# prj1.net
KiCad netlist of a schematic drawn in Altium Designer
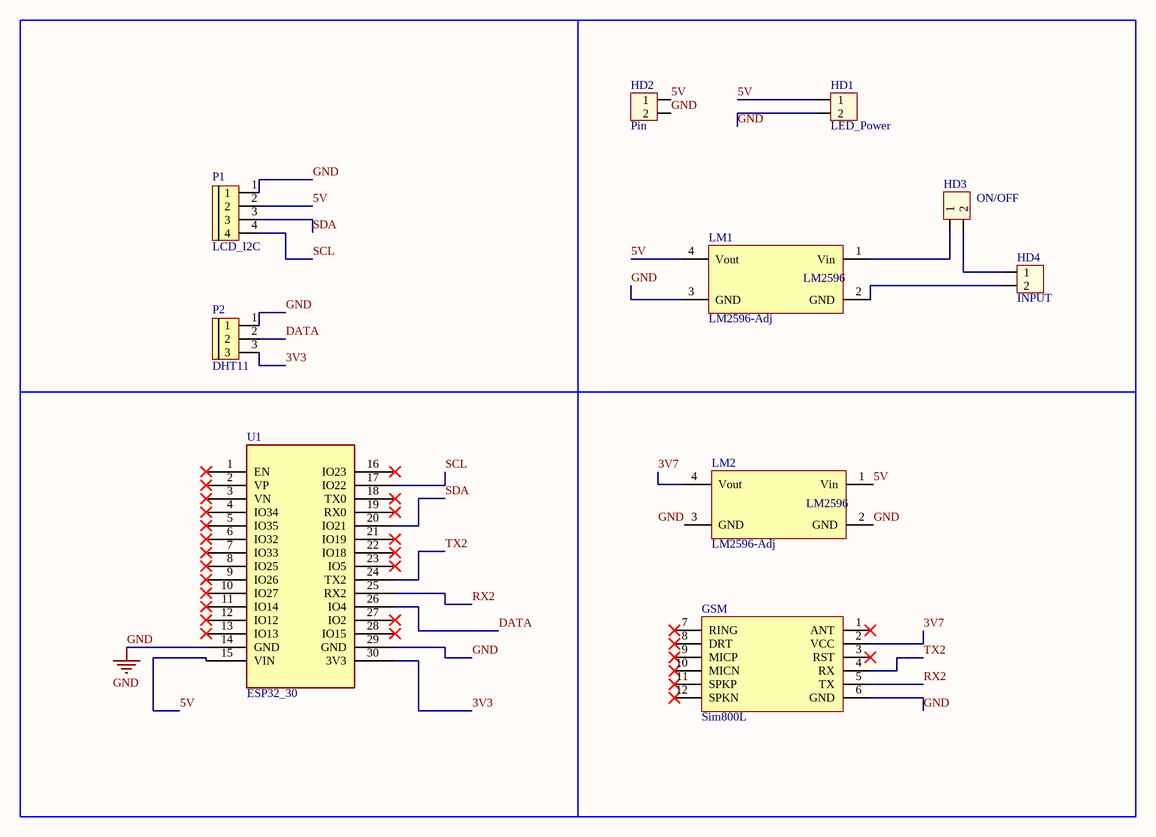
[diagram p0: prj1.SchDoc]

(export (version "E")
  (design (tool "Eeschema 10.0.6"))
  (components
    (comp (ref "GSM")
      (value "Sim800L")
      (footprint "Sim800L")
      (libsource (lib "Sim800L_Module") (part "Sim800L"))
    )
    (comp (ref "HD1")
      (value "LED_Power")
      (footprint "HED2")
      (description "Header 2 (Green)")
      (libsource (lib "") (part "Hed2_2"))
    )
    (comp (ref "HD2")
      (value "Pin")
      (footprint "HED2")
      (description "Header 2 (Green)")
      (libsource (lib "syhaunguyen") (part "Hed2"))
    )
    (comp (ref "HD3")
      (value "ON/OFF")
      (footprint "HED2")
      (description "Header 2 (Green)")
      (libsource (lib "") (part "Hed2_1"))
    )
    (comp (ref "HD4")
      (value "INPUT")
      (footprint "HED2")
      (description "Header 2 (Green)")
      (libsource (lib "") (part "Hed2_2"))
    )
    (comp (ref "LM1")
      (value "LM2596-Adj")
      (footprint "lm2596")
      (description "Designed By @Alixahedi")
      (libsource (lib "LM2596-Adj") (part "LM2596-Adj"))
    )
    (comp (ref "LM2")
      (value "LM2596-Adj")
      (footprint "lm2596")
      (description "Designed By @Alixahedi")
      (libsource (lib "LM2596-Adj") (part "LM2596-Adj"))
    )
    (comp (ref "P1")
      (value "LCD_I2C")
      (footprint "CON 4 4EDG5.08")
      (description "Cắm")
      (libsource (lib "Connector") (part "CON 4 EDG5.08"))
    )
    (comp (ref "P2")
      (value "DHT11")
      (footprint "CON 3 3EDG5.08")
      (description "Cắm")
      (libsource (lib "Connector") (part "CON 3 EDG5.08"))
    )
    (comp (ref "U1")
      (value "ESP32_30")
      (footprint "ESP32_30")
      (description "Microcontoller Board 30 Pins Wifi 2.4GHz BLE 4.2 ESP32-WROOM-32D")
      (libsource (lib "Espressif Microcontrollers") (part "ESP32_30"))
    )
  )
  (nets
    (net (code "1") (name "/3V3") (class "Default")
      (node (ref "P2") (pin "3") (pinfunction "3_3") (pintype "passive"))
      (node (ref "U1") (pin "30") (pinfunction "3V3_30") (pintype "passive"))
    )
    (net (code "2") (name "/3V7") (class "Default")
      (node (ref "GSM") (pin "2") (pinfunction "VCC_2") (pintype "passive"))
      (node (ref "LM2") (pin "4") (pinfunction "Vout_4") (pintype "passive"))
    )
    (net (code "3") (name "/5V") (class "Default")
      (node (ref "HD1") (pin "1") (pinfunction "1_1") (pintype "passive"))
      (node (ref "HD2") (pin "1") (pinfunction "1_1") (pintype "passive"))
      (node (ref "LM1") (pin "4") (pinfunction "Vout_4") (pintype "passive"))
      (node (ref "LM2") (pin "1") (pinfunction "Vin_1") (pintype "passive"))
      (node (ref "P1") (pin "2") (pinfunction "2_2") (pintype "passive"))
      (node (ref "U1") (pin "15") (pinfunction "VIN_15") (pintype "passive"))
    )
    (net (code "4") (name "/DATA") (class "Default")
      (node (ref "P2") (pin "2") (pinfunction "2_2") (pintype "passive"))
      (node (ref "U1") (pin "26") (pinfunction "IO4_26") (pintype "passive"))
    )
    (net (code "5") (name "/RX2") (class "Default")
      (node (ref "GSM") (pin "5") (pinfunction "TX_5") (pintype "passive"))
      (node (ref "U1") (pin "25") (pinfunction "RX2_25") (pintype "passive"))
    )
    (net (code "6") (name "/SCL") (class "Default")
      (node (ref "P1") (pin "4") (pinfunction "4_4") (pintype "passive"))
      (node (ref "U1") (pin "17") (pinfunction "IO22_17") (pintype "passive"))
    )
    (net (code "7") (name "/SDA") (class "Default")
      (node (ref "P1") (pin "3") (pinfunction "3_3") (pintype "passive"))
      (node (ref "U1") (pin "20") (pinfunction "IO21_20") (pintype "passive"))
    )
    (net (code "8") (name "/TX2") (class "Default")
      (node (ref "GSM") (pin "4") (pinfunction "RX_4") (pintype "passive"))
      (node (ref "U1") (pin "24") (pinfunction "TX2_24") (pintype "passive"))
    )
    (net (code "9") (name "GND") (class "Default")
      (node (ref "GSM") (pin "6") (pinfunction "GND_6") (pintype "passive"))
      (node (ref "HD1") (pin "2") (pinfunction "2_2") (pintype "passive"))
      (node (ref "HD2") (pin "2") (pinfunction "2_2") (pintype "passive"))
      (node (ref "LM1") (pin "3") (pinfunction "GND_3") (pintype "passive"))
      (node (ref "LM2") (pin "2") (pinfunction "GND_2") (pintype "passive"))
      (node (ref "P1") (pin "1") (pinfunction "1_1") (pintype "passive"))
      (node (ref "P2") (pin "1") (pinfunction "1_1") (pintype "passive"))
      (node (ref "U1") (pin "14") (pinfunction "GND_14") (pintype "passive"))
      (node (ref "U1") (pin "29") (pinfunction "GND_29") (pintype "passive"))
    )
    (net (code "10") (name "Net-(HD3-Pad2)") (class "Default")
      (node (ref "HD3") (pin "2") (pinfunction "2_2") (pintype "passive"))
      (node (ref "HD4") (pin "1") (pinfunction "1_1") (pintype "passive"))
    )
    (net (code "11") (name "Net-(HD4-Pad2)") (class "Default")
      (node (ref "HD4") (pin "2") (pinfunction "2_2") (pintype "passive"))
      (node (ref "LM1") (pin "2") (pinfunction "GND_2") (pintype "passive"))
    )
    (net (code "12") (name "Net-(LM1-Vin)") (class "Default")
      (node (ref "HD3") (pin "1") (pinfunction "1_1") (pintype "passive"))
      (node (ref "LM1") (pin "1") (pinfunction "Vin_1") (pintype "passive"))
    )
    (net (code "13") (name "unconnected-(GSM-ANT-Pad1)") (class "Default")
      (node (ref "GSM") (pin "1") (pinfunction "ANT_1") (pintype "passive+no_connect"))
    )
    (net (code "14") (name "unconnected-(GSM-DRT-Pad8)") (class "Default")
      (node (ref "GSM") (pin "8") (pinfunction "DRT_8") (pintype "passive+no_connect"))
    )
    (net (code "15") (name "unconnected-(GSM-MICN-Pad10)") (class "Default")
      (node (ref "GSM") (pin "10") (pinfunction "MICN_10") (pintype "passive+no_connect"))
    )
    (net (code "16") (name "unconnected-(GSM-MICP-Pad9)") (class "Default")
      (node (ref "GSM") (pin "9") (pinfunction "MICP_9") (pintype "passive+no_connect"))
    )
    (net (code "17") (name "unconnected-(GSM-RING-Pad7)") (class "Default")
      (node (ref "GSM") (pin "7") (pinfunction "RING_7") (pintype "passive+no_connect"))
    )
    (net (code "18") (name "unconnected-(GSM-RST-Pad3)") (class "Default")
      (node (ref "GSM") (pin "3") (pinfunction "RST_3") (pintype "passive+no_connect"))
    )
    (net (code "19") (name "unconnected-(GSM-SPKN-Pad12)") (class "Default")
      (node (ref "GSM") (pin "12") (pinfunction "SPKN_12") (pintype "passive+no_connect"))
    )
    (net (code "20") (name "unconnected-(GSM-SPKP-Pad11)") (class "Default")
      (node (ref "GSM") (pin "11") (pinfunction "SPKP_11") (pintype "passive+no_connect"))
    )
    (net (code "21") (name "unconnected-(LM2-GND-Pad3)") (class "Default")
      (node (ref "LM2") (pin "3") (pinfunction "GND_3") (pintype "passive"))
    )
    (net (code "22") (name "unconnected-(U1-EN-Pad1)") (class "Default")
      (node (ref "U1") (pin "1") (pinfunction "EN_1") (pintype "passive+no_connect"))
    )
    (net (code "23") (name "unconnected-(U1-IO2-Pad27)") (class "Default")
      (node (ref "U1") (pin "27") (pinfunction "IO2_27") (pintype "passive+no_connect"))
    )
    (net (code "24") (name "unconnected-(U1-IO5-Pad23)") (class "Default")
      (node (ref "U1") (pin "23") (pinfunction "IO5_23") (pintype "passive+no_connect"))
    )
    (net (code "25") (name "unconnected-(U1-IO12-Pad12)") (class "Default")
      (node (ref "U1") (pin "12") (pinfunction "IO12_12") (pintype "passive+no_connect"))
    )
    (net (code "26") (name "unconnected-(U1-IO13-Pad13)") (class "Default")
      (node (ref "U1") (pin "13") (pinfunction "IO13_13") (pintype "passive+no_connect"))
    )
    (net (code "27") (name "unconnected-(U1-IO14-Pad11)") (class "Default")
      (node (ref "U1") (pin "11") (pinfunction "IO14_11") (pintype "passive+no_connect"))
    )
    (net (code "28") (name "unconnected-(U1-IO15-Pad28)") (class "Default")
      (node (ref "U1") (pin "28") (pinfunction "IO15_28") (pintype "passive+no_connect"))
    )
    (net (code "29") (name "unconnected-(U1-IO18-Pad22)") (class "Default")
      (node (ref "U1") (pin "22") (pinfunction "IO18_22") (pintype "passive+no_connect"))
    )
    (net (code "30") (name "unconnected-(U1-IO19-Pad21)") (class "Default")
      (node (ref "U1") (pin "21") (pinfunction "IO19_21") (pintype "passive+no_connect"))
    )
    (net (code "31") (name "unconnected-(U1-IO23-Pad16)") (class "Default")
      (node (ref "U1") (pin "16") (pinfunction "IO23_16") (pintype "passive+no_connect"))
    )
    (net (code "32") (name "unconnected-(U1-IO25-Pad8)") (class "Default")
      (node (ref "U1") (pin "8") (pinfunction "IO25_8") (pintype "passive+no_connect"))
    )
    (net (code "33") (name "unconnected-(U1-IO26-Pad9)") (class "Default")
      (node (ref "U1") (pin "9") (pinfunction "IO26_9") (pintype "passive+no_connect"))
    )
    (net (code "34") (name "unconnected-(U1-IO27-Pad10)") (class "Default")
      (node (ref "U1") (pin "10") (pinfunction "IO27_10") (pintype "passive+no_connect"))
    )
    (net (code "35") (name "unconnected-(U1-IO32-Pad6)") (class "Default")
      (node (ref "U1") (pin "6") (pinfunction "IO32_6") (pintype "passive+no_connect"))
    )
    (net (code "36") (name "unconnected-(U1-IO33-Pad7)") (class "Default")
      (node (ref "U1") (pin "7") (pinfunction "IO33_7") (pintype "passive+no_connect"))
    )
    (net (code "37") (name "unconnected-(U1-IO34-Pad4)") (class "Default")
      (node (ref "U1") (pin "4") (pinfunction "IO34_4") (pintype "passive+no_connect"))
    )
    (net (code "38") (name "unconnected-(U1-IO35-Pad5)") (class "Default")
      (node (ref "U1") (pin "5") (pinfunction "IO35_5") (pintype "passive+no_connect"))
    )
    (net (code "39") (name "unconnected-(U1-RX0-Pad19)") (class "Default")
      (node (ref "U1") (pin "19") (pinfunction "RX0_19") (pintype "passive+no_connect"))
    )
    (net (code "40") (name "unconnected-(U1-TX0-Pad18)") (class "Default")
      (node (ref "U1") (pin "18") (pinfunction "TX0_18") (pintype "passive+no_connect"))
    )
    (net (code "41") (name "unconnected-(U1-VN-Pad3)") (class "Default")
      (node (ref "U1") (pin "3") (pinfunction "VN_3") (pintype "passive+no_connect"))
    )
    (net (code "42") (name "unconnected-(U1-VP-Pad2)") (class "Default")
      (node (ref "U1") (pin "2") (pinfunction "VP_2") (pintype "passive+no_connect"))
    )
  )
)
